# Serqet_FS_U_01.net
KiCad netlist of a schematic drawn in Altium Designer
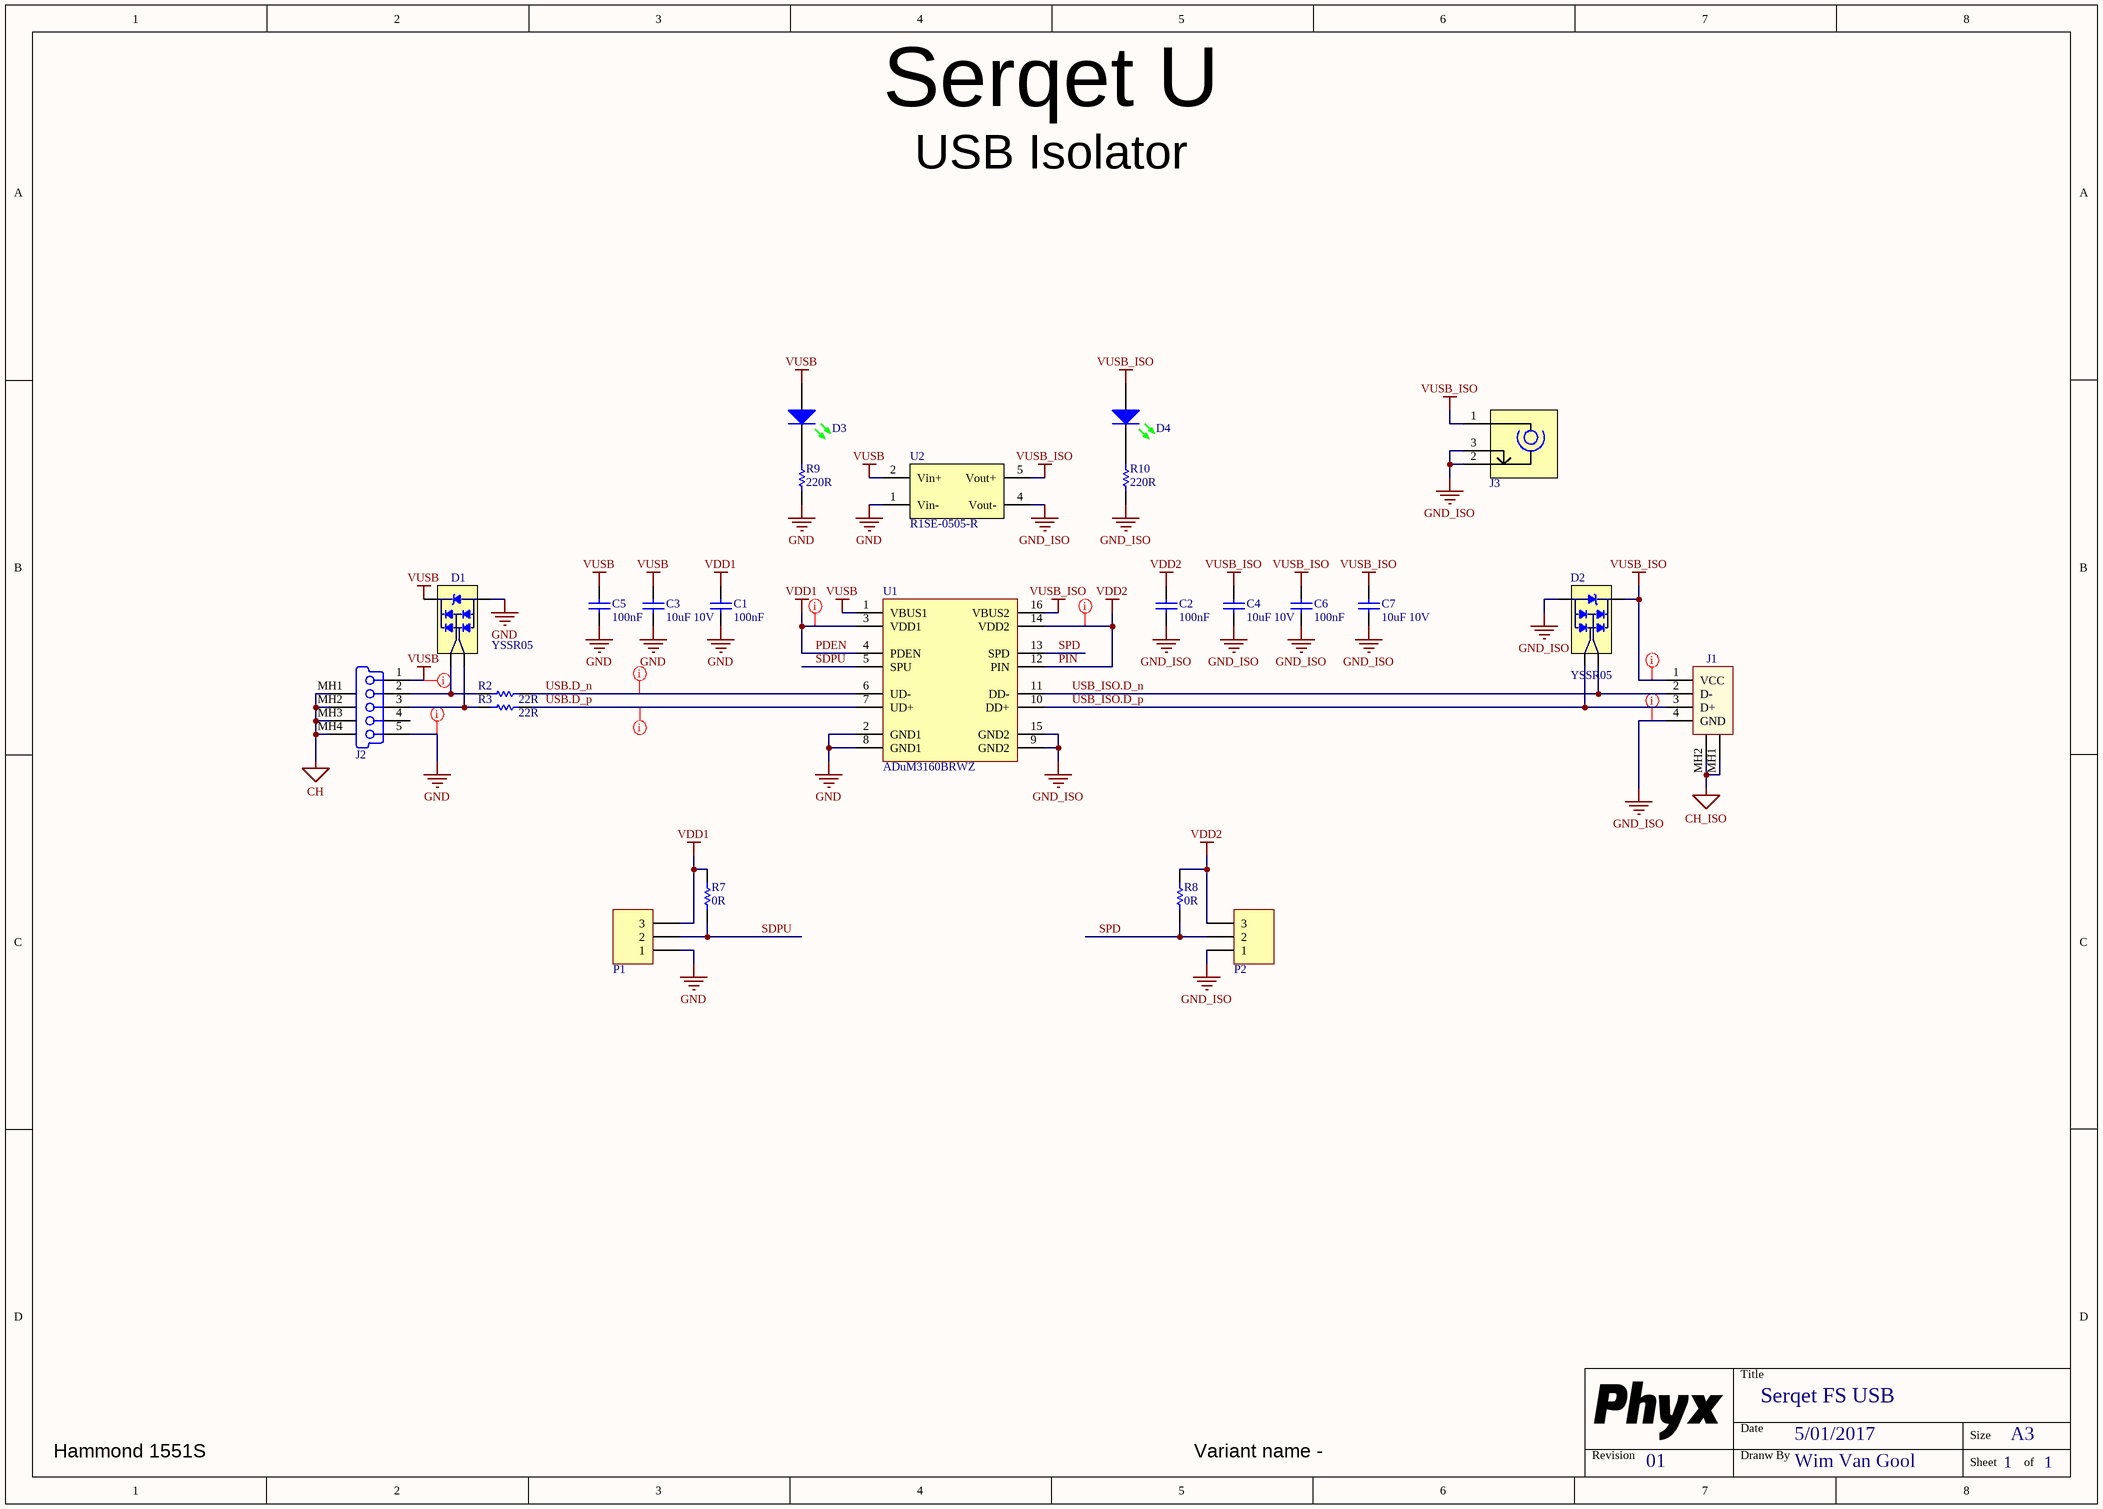
[diagram p0: Serqet_FS_U_01.SchDoc]

(export (version "E")
  (design (tool "Eeschema 10.0.6"))
  (components
    (comp (ref "C1")
      (value "100nF")
      (footprint "C0603_N")
      (description "Capacitor Ceramic")
      (fields (field (name "Comment") "CAP_CERAMIC"))
      (libsource (lib "Phyx_Components") (part "CAP_CERAMIC"))
    )
    (comp (ref "C2")
      (value "100nF")
      (footprint "C0603_N")
      (description "Capacitor Ceramic")
      (fields (field (name "Comment") "CAP_CERAMIC"))
      (libsource (lib "Phyx_Components") (part "CAP_CERAMIC"))
    )
    (comp (ref "C3")
      (value "10uF 10V")
      (footprint "C0805_N")
      (description "Capacitor Ceramic")
      (fields (field (name "Comment") "CAP_CERAMIC"))
      (libsource (lib "Phyx_Components") (part "CAP_CERAMIC"))
    )
    (comp (ref "C4")
      (value "10uF 10V")
      (footprint "C0805_N")
      (description "Capacitor Ceramic")
      (fields (field (name "Comment") "CAP_CERAMIC"))
      (libsource (lib "Phyx_Components") (part "CAP_CERAMIC"))
    )
    (comp (ref "C5")
      (value "100nF")
      (footprint "C0603_N")
      (description "Capacitor Ceramic")
      (fields (field (name "Comment") "CAP_CERAMIC"))
      (libsource (lib "Phyx_Components") (part "CAP_CERAMIC"))
    )
    (comp (ref "C6")
      (value "100nF")
      (footprint "C0603_N")
      (description "Capacitor Ceramic")
      (fields (field (name "Comment") "CAP_CERAMIC"))
      (libsource (lib "Phyx_Components") (part "CAP_CERAMIC"))
    )
    (comp (ref "C7")
      (value "10uF 10V")
      (footprint "C0805_N")
      (description "Capacitor Ceramic")
      (fields (field (name "Comment") "CAP_CERAMIC"))
      (libsource (lib "Phyx_Components") (part "CAP_CERAMIC"))
    )
    (comp (ref "D1")
      (value "YSSR05")
      (footprint "SOT-143")
      (description "=Description")
      (fields (field (name "Comment") "Low Capacitanse TVS Diode array"))
      (libsource (lib "") (part "YSSR05_1"))
    )
    (comp (ref "D2")
      (value "YSSR05")
      (footprint "SOT-143")
      (description "=Description")
      (fields (field (name "Comment") "Low Capacitanse TVS Diode array"))
      (libsource (lib "Phyx_Components") (part "YSSR05"))
    )
    (comp (ref "D3")
      (value "Default 0805 Green LED")
      (footprint "LED_0805_GR")
      (description "=Description")
      (libsource (lib "Phyx_Components") (part "LED_GREEN"))
    )
    (comp (ref "D4")
      (value "Default 0805 Green LED")
      (footprint "LED_0805_GR")
      (description "=Description")
      (libsource (lib "Phyx_Components") (part "LED_GREEN"))
    )
    (comp (ref "J1")
      (value "USB type A Short horizontal connector")
      (footprint "WE_614104150121")
      (libsource (lib "Phyx_Components") (part "USB_A"))
    )
    (comp (ref "J2")
      (value "THT USB Mini-B Receptacle")
      (footprint "USB_Mini-B_THT")
      (libsource (lib "Phyx_Components") (part "USB_OTG_Mini-B"))
    )
    (comp (ref "J3")
      (value "Socket RA 3.5 with 1.35 barrel")
      (footprint "DC-003")
      (description "=Description")
      (libsource (lib "Phyx_Components") (part "Cliff_DC10"))
    )
    (comp (ref "P1") (value "Header 3") (footprint "HDR1X3") (libsource (lib "") (part "Header 3_1")))
    (comp (ref "P2")
      (value "Header 3")
      (footprint "HDR1X3")
      (libsource (lib "Phyx_Components") (part "Header 3"))
    )
    (comp (ref "R2")
      (value "22R")
      (footprint "R0603_N")
      (fields (field (name "Comment") "RESISTOR"))
      (libsource (lib "Phyx_Components") (part "RESISTOR"))
    )
    (comp (ref "R3")
      (value "22R")
      (footprint "R0603_N")
      (fields (field (name "Comment") "RESISTOR"))
      (libsource (lib "Phyx_Components") (part "RESISTOR"))
    )
    (comp (ref "R7")
      (value "0R")
      (footprint "R0603_N")
      (fields (field (name "Comment") "RESISTOR"))
      (libsource (lib "Phyx_Components") (part "RESISTOR"))
    )
    (comp (ref "R8")
      (value "0R")
      (footprint "R0603_N")
      (fields (field (name "Comment") "RESISTOR"))
      (libsource (lib "Phyx_Components") (part "RESISTOR"))
    )
    (comp (ref "R9")
      (value "220R")
      (footprint "R0603_N")
      (fields (field (name "Comment") "RESISTOR"))
      (libsource (lib "Phyx_Components") (part "RESISTOR"))
    )
    (comp (ref "R10")
      (value "220R")
      (footprint "R0603_N")
      (fields (field (name "Comment") "RESISTOR"))
      (libsource (lib "Phyx_Components") (part "RESISTOR"))
    )
    (comp (ref "U1")
      (value "ADuM3160BRWZ")
      (footprint "SOIC_W_16")
      (description "=Description")
      (fields (field (name "Comment") "USB FS 12Mbps isolator 2,5kV"))
      (libsource (lib "Phyx_Components") (part "ADUM3160"))
    )
    (comp (ref "U2")
      (value "R1SE-0505-R")
      (footprint "R1SE-0505-R")
      (description "=Description")
      (fields (field (name "Comment") "Isolated DC-DC module 1kV 5V 1W"))
      (libsource (lib "Phyx_Components") (part "R1SE-0505-R"))
    )
  )
  (nets
    (net (code "1") (name "/SDPU") (class "Default")
      (node (ref "P1") (pin "2") (pinfunction "2_2") (pintype "passive"))
      (node (ref "R7") (pin "2") (pinfunction "2_2") (pintype "passive"))
      (node (ref "U1") (pin "5") (pinfunction "SPU_5") (pintype "passive"))
    )
    (net (code "2") (name "/SPD") (class "Default")
      (node (ref "P2") (pin "2") (pinfunction "2_2") (pintype "passive"))
      (node (ref "R8") (pin "2") (pinfunction "2_2") (pintype "passive"))
      (node (ref "U1") (pin "13") (pinfunction "SPD_13") (pintype "passive"))
    )
    (net (code "3") (name "/USB.D_n") (class "Default")
      (node (ref "R2") (pin "1") (pinfunction "1_1") (pintype "passive"))
      (node (ref "U1") (pin "6") (pinfunction "UD-_6") (pintype "passive"))
    )
    (net (code "4") (name "/USB.D_p") (class "Default")
      (node (ref "R3") (pin "1") (pinfunction "1_1") (pintype "passive"))
      (node (ref "U1") (pin "7") (pinfunction "UD+_7") (pintype "passive"))
    )
    (net (code "5") (name "/USB_ISO.D_n") (class "Default")
      (node (ref "D2") (pin "3") (pinfunction "3_3") (pintype "passive"))
      (node (ref "J1") (pin "2") (pinfunction "D-_2") (pintype "passive"))
      (node (ref "U1") (pin "11") (pinfunction "DD-_11") (pintype "passive"))
    )
    (net (code "6") (name "/USB_ISO.D_p") (class "Default")
      (node (ref "D2") (pin "2") (pinfunction "2_2") (pintype "passive"))
      (node (ref "J1") (pin "3") (pinfunction "D+_3") (pintype "passive"))
      (node (ref "U1") (pin "10") (pinfunction "DD+_10") (pintype "passive"))
    )
    (net (code "7") (name "CH") (class "Default")
      (node (ref "J2") (pin "MH1") (pinfunction "Tab_MH1") (pintype "passive"))
      (node (ref "J2") (pin "MH2") (pinfunction "Tab_MH2") (pintype "passive"))
      (node (ref "J2") (pin "MH3") (pinfunction "Tab_MH3") (pintype "passive"))
      (node (ref "J2") (pin "MH4") (pinfunction "Tab_MH4") (pintype "passive"))
    )
    (net (code "8") (name "CH_ISO") (class "Default")
      (node (ref "J1") (pin "MH1") (pinfunction "Tab_MH1") (pintype "passive"))
      (node (ref "J1") (pin "MH2") (pinfunction "Tab_MH2") (pintype "passive"))
    )
    (net (code "9") (name "GND") (class "Default")
      (node (ref "C1") (pin "2") (pinfunction "2_2") (pintype "passive"))
      (node (ref "C3") (pin "2") (pinfunction "2_2") (pintype "passive"))
      (node (ref "C5") (pin "2") (pinfunction "2_2") (pintype "passive"))
      (node (ref "D1") (pin "1") (pinfunction "1_1") (pintype "passive"))
      (node (ref "J2") (pin "5") (pinfunction "GND_5") (pintype "passive"))
      (node (ref "P1") (pin "1") (pinfunction "1_1") (pintype "passive"))
      (node (ref "R9") (pin "2") (pinfunction "2_2") (pintype "passive"))
      (node (ref "U1") (pin "2") (pinfunction "GND1_2") (pintype "passive"))
      (node (ref "U1") (pin "8") (pinfunction "GND1_8") (pintype "passive"))
      (node (ref "U2") (pin "1") (pinfunction "Vin-_1") (pintype "power_in"))
    )
    (net (code "10") (name "GND_ISO") (class "Default")
      (node (ref "C2") (pin "2") (pinfunction "2_2") (pintype "passive"))
      (node (ref "C4") (pin "2") (pinfunction "2_2") (pintype "passive"))
      (node (ref "C6") (pin "2") (pinfunction "2_2") (pintype "passive"))
      (node (ref "C7") (pin "2") (pinfunction "2_2") (pintype "passive"))
      (node (ref "D2") (pin "1") (pinfunction "1_1") (pintype "passive"))
      (node (ref "J1") (pin "4") (pinfunction "GND_4") (pintype "passive"))
      (node (ref "J3") (pin "2") (pinfunction "2_2") (pintype "passive"))
      (node (ref "J3") (pin "3") (pinfunction "3_3") (pintype "passive"))
      (node (ref "P2") (pin "1") (pinfunction "1_1") (pintype "passive"))
      (node (ref "R10") (pin "2") (pinfunction "2_2") (pintype "passive"))
      (node (ref "U1") (pin "15") (pinfunction "GND2_15") (pintype "passive"))
      (node (ref "U1") (pin "9") (pinfunction "GND2_9") (pintype "passive"))
      (node (ref "U2") (pin "4") (pinfunction "Vout-_4") (pintype "power_in"))
    )
    (net (code "11") (name "Net-(D3-K)") (class "Default")
      (node (ref "D3") (pin "2") (pinfunction "K_2") (pintype "passive"))
      (node (ref "R9") (pin "1") (pinfunction "1_1") (pintype "passive"))
    )
    (net (code "12") (name "Net-(D4-K)") (class "Default")
      (node (ref "D4") (pin "2") (pinfunction "K_2") (pintype "passive"))
      (node (ref "R10") (pin "1") (pinfunction "1_1") (pintype "passive"))
    )
    (net (code "13") (name "Net-(J2-D+)") (class "Default")
      (node (ref "D1") (pin "2") (pinfunction "2_2") (pintype "passive"))
      (node (ref "J2") (pin "3") (pinfunction "D+_3") (pintype "passive"))
      (node (ref "R3") (pin "2") (pinfunction "2_2") (pintype "passive"))
    )
    (net (code "14") (name "Net-(J2-D-)") (class "Default")
      (node (ref "D1") (pin "3") (pinfunction "3_3") (pintype "passive"))
      (node (ref "J2") (pin "2") (pinfunction "D-_2") (pintype "passive"))
      (node (ref "R2") (pin "2") (pinfunction "2_2") (pintype "passive"))
    )
    (net (code "15") (name "VDD1") (class "Default")
      (node (ref "C1") (pin "1") (pinfunction "1_1") (pintype "passive"))
      (node (ref "P1") (pin "3") (pinfunction "3_3") (pintype "passive"))
      (node (ref "R7") (pin "1") (pinfunction "1_1") (pintype "passive"))
      (node (ref "U1") (pin "3") (pinfunction "VDD1_3") (pintype "passive"))
      (node (ref "U1") (pin "4") (pinfunction "PDEN_4") (pintype "passive"))
    )
    (net (code "16") (name "VDD2") (class "Default")
      (node (ref "C2") (pin "1") (pinfunction "1_1") (pintype "passive"))
      (node (ref "P2") (pin "3") (pinfunction "3_3") (pintype "passive"))
      (node (ref "R8") (pin "1") (pinfunction "1_1") (pintype "passive"))
      (node (ref "U1") (pin "12") (pinfunction "PIN_12") (pintype "passive"))
      (node (ref "U1") (pin "14") (pinfunction "VDD2_14") (pintype "passive"))
    )
    (net (code "17") (name "VUSB") (class "Default")
      (node (ref "C3") (pin "1") (pinfunction "1_1") (pintype "passive"))
      (node (ref "C5") (pin "1") (pinfunction "1_1") (pintype "passive"))
      (node (ref "D1") (pin "4") (pinfunction "4_4") (pintype "passive"))
      (node (ref "D3") (pin "1") (pinfunction "A_1") (pintype "passive"))
      (node (ref "J2") (pin "1") (pinfunction "V_BUS_(5V)_1") (pintype "passive"))
      (node (ref "U1") (pin "1") (pinfunction "VBUS1_1") (pintype "passive"))
      (node (ref "U2") (pin "2") (pinfunction "Vin+_2") (pintype "power_in"))
    )
    (net (code "18") (name "VUSB_ISO") (class "Default")
      (node (ref "C4") (pin "1") (pinfunction "1_1") (pintype "passive"))
      (node (ref "C6") (pin "1") (pinfunction "1_1") (pintype "passive"))
      (node (ref "C7") (pin "1") (pinfunction "1_1") (pintype "passive"))
      (node (ref "D2") (pin "4") (pinfunction "4_4") (pintype "passive"))
      (node (ref "D4") (pin "1") (pinfunction "A_1") (pintype "passive"))
      (node (ref "J1") (pin "1") (pinfunction "VCC_1") (pintype "passive"))
      (node (ref "J3") (pin "1") (pinfunction "1_1") (pintype "passive"))
      (node (ref "U1") (pin "16") (pinfunction "VBUS2_16") (pintype "passive"))
      (node (ref "U2") (pin "5") (pinfunction "Vout+_5") (pintype "power_in"))
    )
    (net (code "19") (name "unconnected-(J2-NC-Pad4)") (class "Default")
      (node (ref "J2") (pin "4") (pinfunction "NC_4") (pintype "passive"))
    )
  )
)
